# Control_de_Juez_V1_0_0_CNC.net
KiCad netlist of a schematic drawn in EAGLE
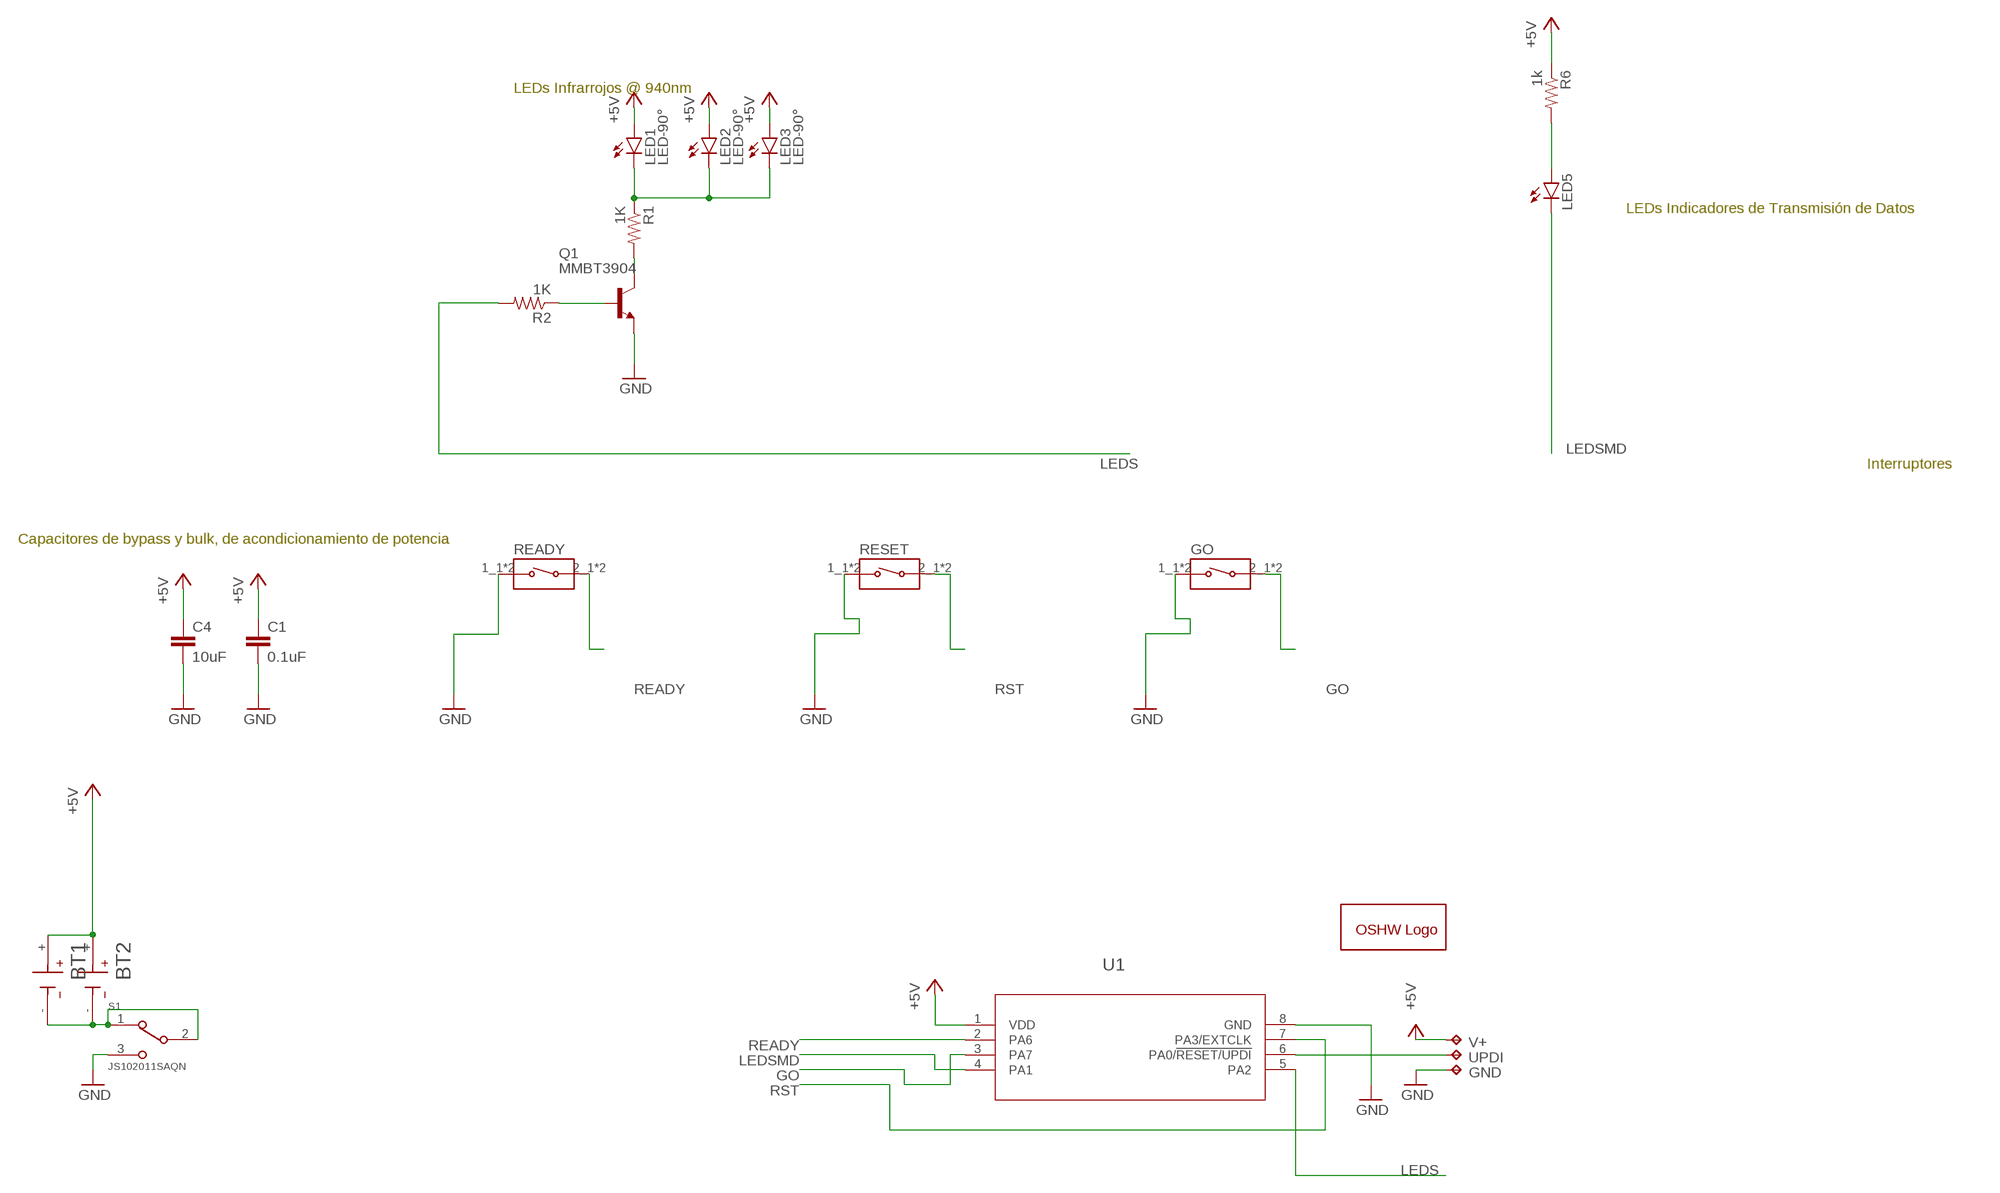
[diagram p0: schematic, sheet 1]

(export (version "E")
  (design (tool "Eeschema 10.0.6"))
  (components
    (comp (ref "BT1")
      (value "BU2032SM-HD-G")
      (footprint "eagle-import:BAT_BU2032SM-HD-G")
      (fields (field (name "MF") "MPD (Memory Protection Devices)"))
      (libsource (lib "eagle-import") (part "BU2032SM-HD-G"))
    )
    (comp (ref "BT2")
      (value "BU2032SM-HD-G")
      (footprint "eagle-import:BAT_BU2032SM-HD-G")
      (fields (field (name "MF") "MPD (Memory Protection Devices)"))
      (libsource (lib "eagle-import") (part "BU2032SM-HD-G"))
    )
    (comp (ref "C1")
      (value "0.1uF")
      (footprint "eagle-import:C0603")
      (libsource (lib "eagle-import") (part "C-EUC0603"))
    )
    (comp (ref "C4")
      (value "10uF")
      (footprint "eagle-import:C0603")
      (libsource (lib "eagle-import") (part "C-EUC0603"))
    )
    (comp (ref "GND")
      (value "TPB1,27")
      (footprint "eagle-import:B1,27")
      (libsource (lib "eagle-import") (part "TPB1,27"))
    )
    (comp (ref "GO")
      (value "EVQ-P7L01P")
      (footprint "eagle-import:SW_EVQ-P7L01P")
      (fields
        (field (name "DIGI-KEY_PART_NUMBER") "P16769CT-ND")
        (field (name "MF") "Panasonic Electronic Components")
      )
      (libsource (lib "eagle-import") (part "EVQ-P7L01P"))
    )
    (comp (ref "GOLD_ORB_SM1")
      (value "OSHWLOGOLOGO8MM")
      (footprint "eagle-import:OSHW_8MM")
      (libsource (lib "eagle-import") (part "OSHWLOGOLOGO8MM"))
    )
    (comp (ref "LED1")
      (value "LED-90°")
      (footprint "eagle-import:LED-90°")
      (libsource (lib "eagle-import") (part "LED-90°"))
    )
    (comp (ref "LED2")
      (value "LED-90°")
      (footprint "eagle-import:LED-90°")
      (libsource (lib "eagle-import") (part "LED-90°"))
    )
    (comp (ref "LED3")
      (value "LED-90°")
      (footprint "eagle-import:LED-90°")
      (libsource (lib "eagle-import") (part "LED-90°"))
    )
    (comp (ref "LED5")
      (value "LEDSML1206")
      (footprint "eagle-import:SML1206")
      (libsource (lib "eagle-import") (part "LEDSML1206"))
    )
    (comp (ref "Q1")
      (value "MMBT3904")
      (footprint "eagle-import:SOT23")
      (libsource (lib "eagle-import") (part "MMBT3904"))
    )
    (comp (ref "R1")
      (value "1K")
      (footprint "eagle-import:R0603")
      (libsource (lib "eagle-import") (part "R-US_R0603"))
    )
    (comp (ref "R2")
      (value "1K")
      (footprint "eagle-import:R0603")
      (libsource (lib "eagle-import") (part "R-US_R0603"))
    )
    (comp (ref "R6")
      (value "1k")
      (footprint "eagle-import:R0603")
      (libsource (lib "eagle-import") (part "R-US_R0603"))
    )
    (comp (ref "READY")
      (value "EVQ-P7L01P")
      (footprint "eagle-import:SW_EVQ-P7L01P")
      (fields
        (field (name "DIGI-KEY_PART_NUMBER") "P16769CT-ND")
        (field (name "MF") "Panasonic Electronic Components")
      )
      (libsource (lib "eagle-import") (part "EVQ-P7L01P"))
    )
    (comp (ref "RESET")
      (value "EVQ-P7L01P")
      (footprint "eagle-import:SW_EVQ-P7L01P")
      (fields
        (field (name "DIGI-KEY_PART_NUMBER") "P16769CT-ND")
        (field (name "MF") "Panasonic Electronic Components")
      )
      (libsource (lib "eagle-import") (part "EVQ-P7L01P"))
    )
    (comp (ref "S1")
      (value "JS102011SAQN")
      (footprint "eagle-import:SW_JS102011SAQN")
      (fields (field (name "DIGI-KEY_PART_NUMBER") "401-1999-1-ND") (field (name "MF") "C&K"))
      (libsource (lib "eagle-import") (part "JS102011SAQN"))
    )
    (comp (ref "U1")
      (value "ATTINY412-SSNSOIC8_SA_SST_MCH-M")
      (footprint "eagle-import:SOIC8_SA_SST_MCH-M")
      (fields
        (field (name "MANUFACTURER_PART_NUMBER") "ATTINY412-SSN")
        (field (name "COPYRIGHT") "Copyright (C) 2018 Accelerated Designs. All rights reserved")
      )
      (libsource (lib "eagle-import") (part "ATTINY412-SSNSOIC8_SA_SST_MCH-M"))
    )
    (comp (ref "UPDI")
      (value "TPB1,27")
      (footprint "eagle-import:B1,27")
      (libsource (lib "eagle-import") (part "TPB1,27"))
    )
    (comp (ref "V+")
      (value "TPB1,27")
      (footprint "eagle-import:B1,27")
      (libsource (lib "eagle-import") (part "TPB1,27"))
    )
  )
  (nets
    (net (code "1") (name "+5V") (class "Default")
      (node (ref "BT1") (pin "+") (pinfunction "+_+") (pintype "passive"))
      (node (ref "BT2") (pin "+") (pinfunction "+_+") (pintype "passive"))
      (node (ref "C1") (pin "1") (pinfunction "1_1") (pintype "passive"))
      (node (ref "C4") (pin "1") (pinfunction "1_1") (pintype "passive"))
      (node (ref "LED1") (pin "1") (pinfunction "A_1") (pintype "passive"))
      (node (ref "LED2") (pin "1") (pinfunction "A_1") (pintype "passive"))
      (node (ref "LED3") (pin "1") (pinfunction "A_1") (pintype "passive"))
      (node (ref "R6") (pin "1") (pinfunction "1_1") (pintype "passive"))
      (node (ref "U1") (pin "1") (pinfunction "VDD_1") (pintype "power_in"))
      (node (ref "V+") (pin "TP") (pinfunction "TP_TP") (pintype "input"))
    )
    (net (code "2") (name "/GO") (class "Default")
      (node (ref "GO") (pin "2_1") (pinfunction "2_2_1") (pintype "passive"))
      (node (ref "GO") (pin "2_2") (pinfunction "2_2_2") (pintype "passive"))
      (node (ref "U1") (pin "3") (pinfunction "PA7_3") (pintype "bidirectional"))
    )
    (net (code "3") (name "/LEDS") (class "Default")
      (node (ref "R2") (pin "2") (pinfunction "2_2") (pintype "passive"))
      (node (ref "U1") (pin "5") (pinfunction "PA2_5") (pintype "bidirectional"))
    )
    (net (code "4") (name "/LEDSMD") (class "Default")
      (node (ref "LED5") (pin "C") (pinfunction "C_C") (pintype "passive"))
      (node (ref "U1") (pin "4") (pinfunction "PA1_4") (pintype "bidirectional"))
    )
    (net (code "5") (name "/READY") (class "Default")
      (node (ref "READY") (pin "2_1") (pinfunction "2_2_1") (pintype "passive"))
      (node (ref "READY") (pin "2_2") (pinfunction "2_2_2") (pintype "passive"))
      (node (ref "U1") (pin "2") (pinfunction "PA6_2") (pintype "bidirectional"))
    )
    (net (code "6") (name "/RST") (class "Default")
      (node (ref "RESET") (pin "2_1") (pinfunction "2_2_1") (pintype "passive"))
      (node (ref "RESET") (pin "2_2") (pinfunction "2_2_2") (pintype "passive"))
      (node (ref "U1") (pin "7") (pinfunction "PA3/EXTCLK_7") (pintype "bidirectional"))
    )
    (net (code "7") (name "GND") (class "Default")
      (node (ref "C1") (pin "2") (pinfunction "2_2") (pintype "passive"))
      (node (ref "C4") (pin "2") (pinfunction "2_2") (pintype "passive"))
      (node (ref "GND") (pin "TP") (pinfunction "TP_TP") (pintype "input"))
      (node (ref "GO") (pin "1_1") (pinfunction "1_1_1") (pintype "passive"))
      (node (ref "GO") (pin "1_2") (pinfunction "1_1_2") (pintype "passive"))
      (node (ref "Q1") (pin "E") (pinfunction "E_E") (pintype "passive"))
      (node (ref "READY") (pin "1_1") (pinfunction "1_1_1") (pintype "passive"))
      (node (ref "READY") (pin "1_2") (pinfunction "1_1_2") (pintype "passive"))
      (node (ref "RESET") (pin "1_1") (pinfunction "1_1_1") (pintype "passive"))
      (node (ref "RESET") (pin "1_2") (pinfunction "1_1_2") (pintype "passive"))
      (node (ref "S1") (pin "3") (pinfunction "3_3") (pintype "passive"))
      (node (ref "U1") (pin "8") (pinfunction "GND_8") (pintype "passive"))
    )
    (net (code "8") (name "Net-(BT1-Pad-)") (class "Default")
      (node (ref "BT1") (pin "-") (pinfunction "-_-") (pintype "passive"))
      (node (ref "BT2") (pin "-") (pinfunction "-_-") (pintype "passive"))
      (node (ref "S1") (pin "1") (pinfunction "1_1") (pintype "passive"))
      (node (ref "S1") (pin "2") (pinfunction "2_2") (pintype "passive"))
    )
    (net (code "9") (name "Net-(LED1-C)") (class "Default")
      (node (ref "LED1") (pin "2") (pinfunction "C_2") (pintype "passive"))
      (node (ref "LED2") (pin "2") (pinfunction "C_2") (pintype "passive"))
      (node (ref "LED3") (pin "2") (pinfunction "C_2") (pintype "passive"))
      (node (ref "R1") (pin "1") (pinfunction "1_1") (pintype "passive"))
    )
    (net (code "10") (name "Net-(LED5-PadA)") (class "Default")
      (node (ref "LED5") (pin "A") (pinfunction "A_A") (pintype "passive"))
      (node (ref "R6") (pin "2") (pinfunction "2_2") (pintype "passive"))
    )
    (net (code "11") (name "Net-(Q1-PadB)") (class "Default")
      (node (ref "Q1") (pin "B") (pinfunction "B_B") (pintype "passive"))
      (node (ref "R2") (pin "1") (pinfunction "1_1") (pintype "passive"))
    )
    (net (code "12") (name "Net-(Q1-PadC)") (class "Default")
      (node (ref "Q1") (pin "C") (pinfunction "C_C") (pintype "passive"))
      (node (ref "R1") (pin "2") (pinfunction "2_2") (pintype "passive"))
    )
    (net (code "13") (name "Net-(U1-PA0{slash}~{RESET{slash}UPDI})") (class "Default")
      (node (ref "U1") (pin "6") (pinfunction "PA0/~{RESET/UPDI}_6") (pintype "bidirectional"))
      (node (ref "UPDI") (pin "TP") (pinfunction "TP_TP") (pintype "input"))
    )
  )
)
